# 04_HDMI_MIPI.net
KiCad netlist of a schematic drawn in Altium Designer
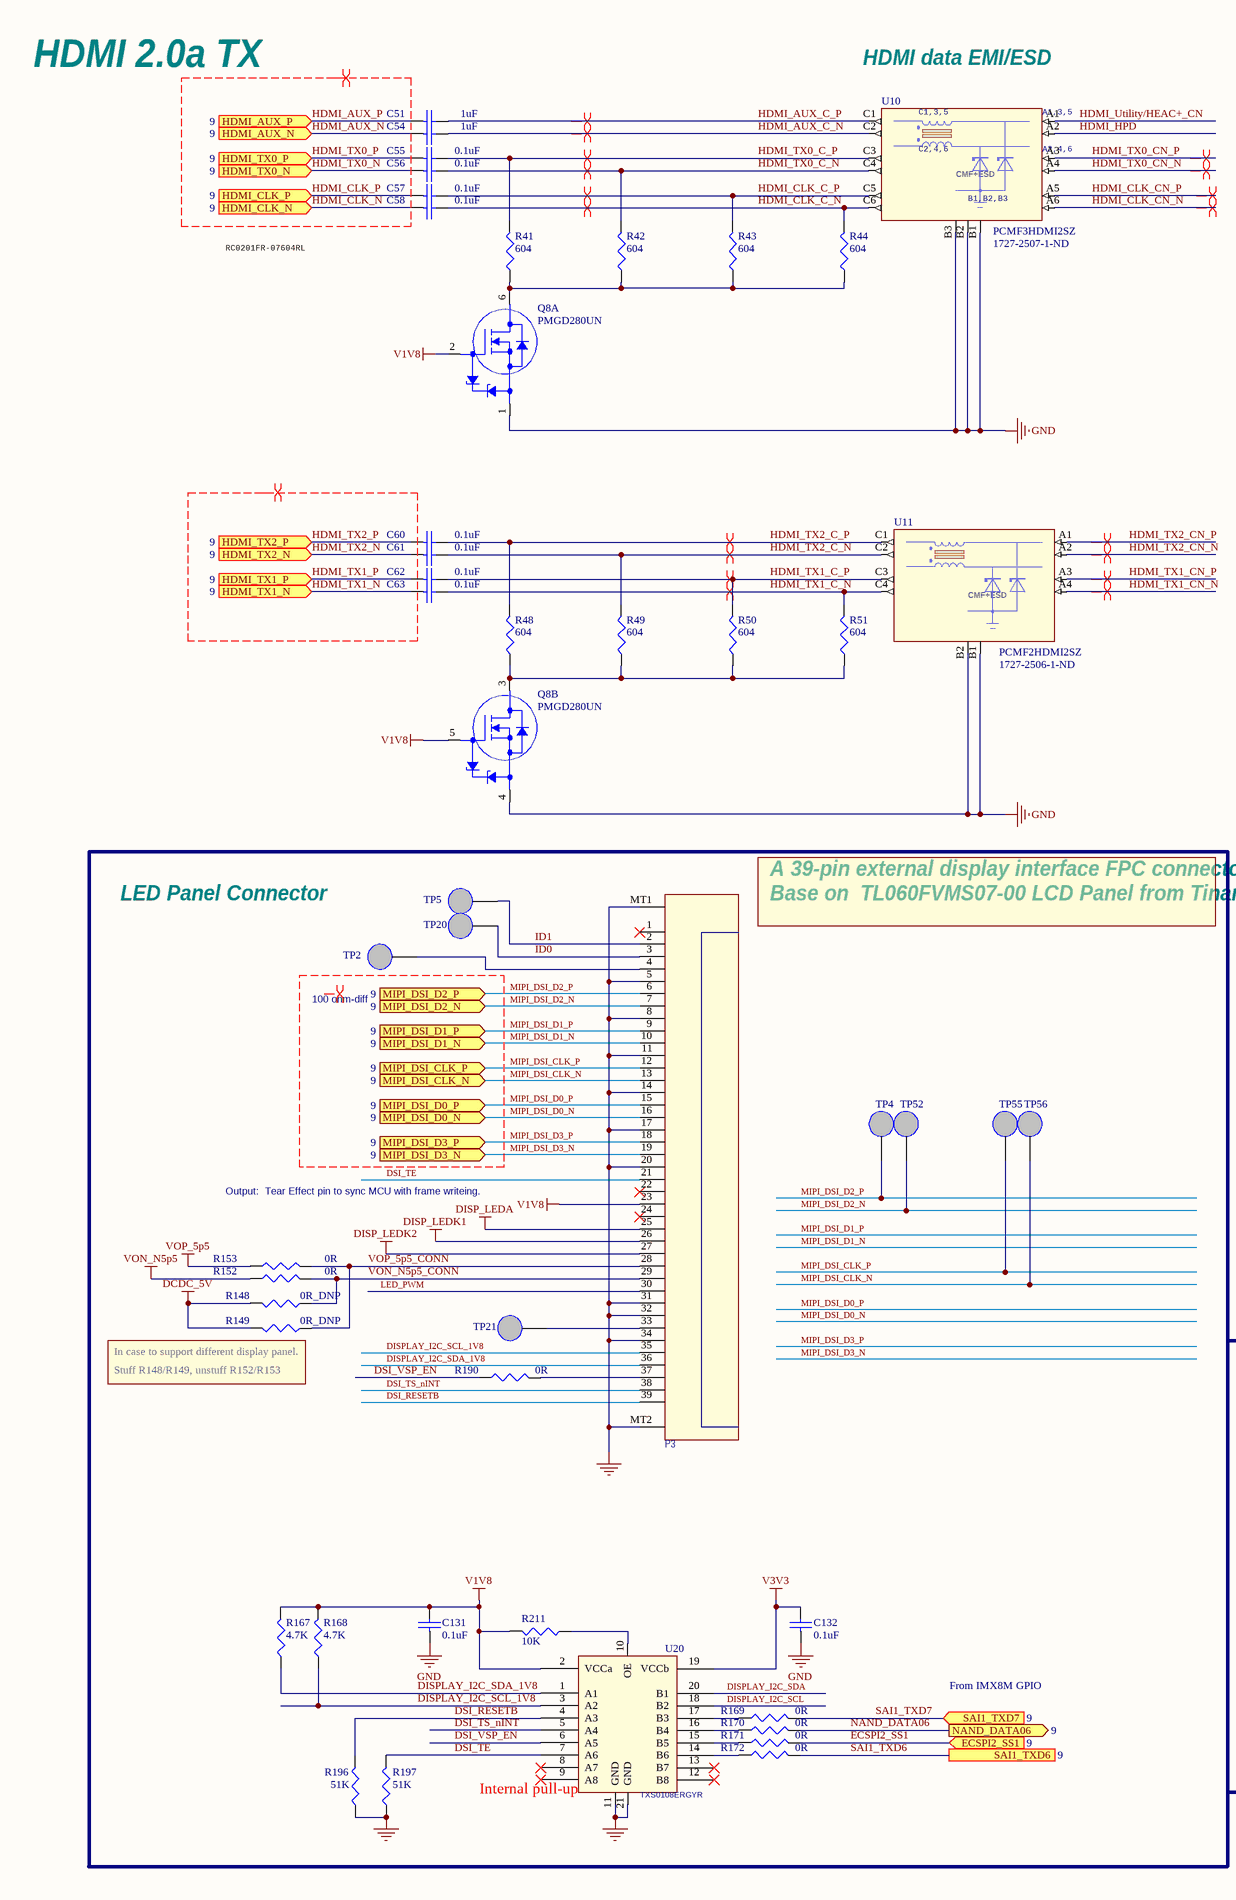
[diagram p0: 04_HDMI_MIPI.SchDoc, left]
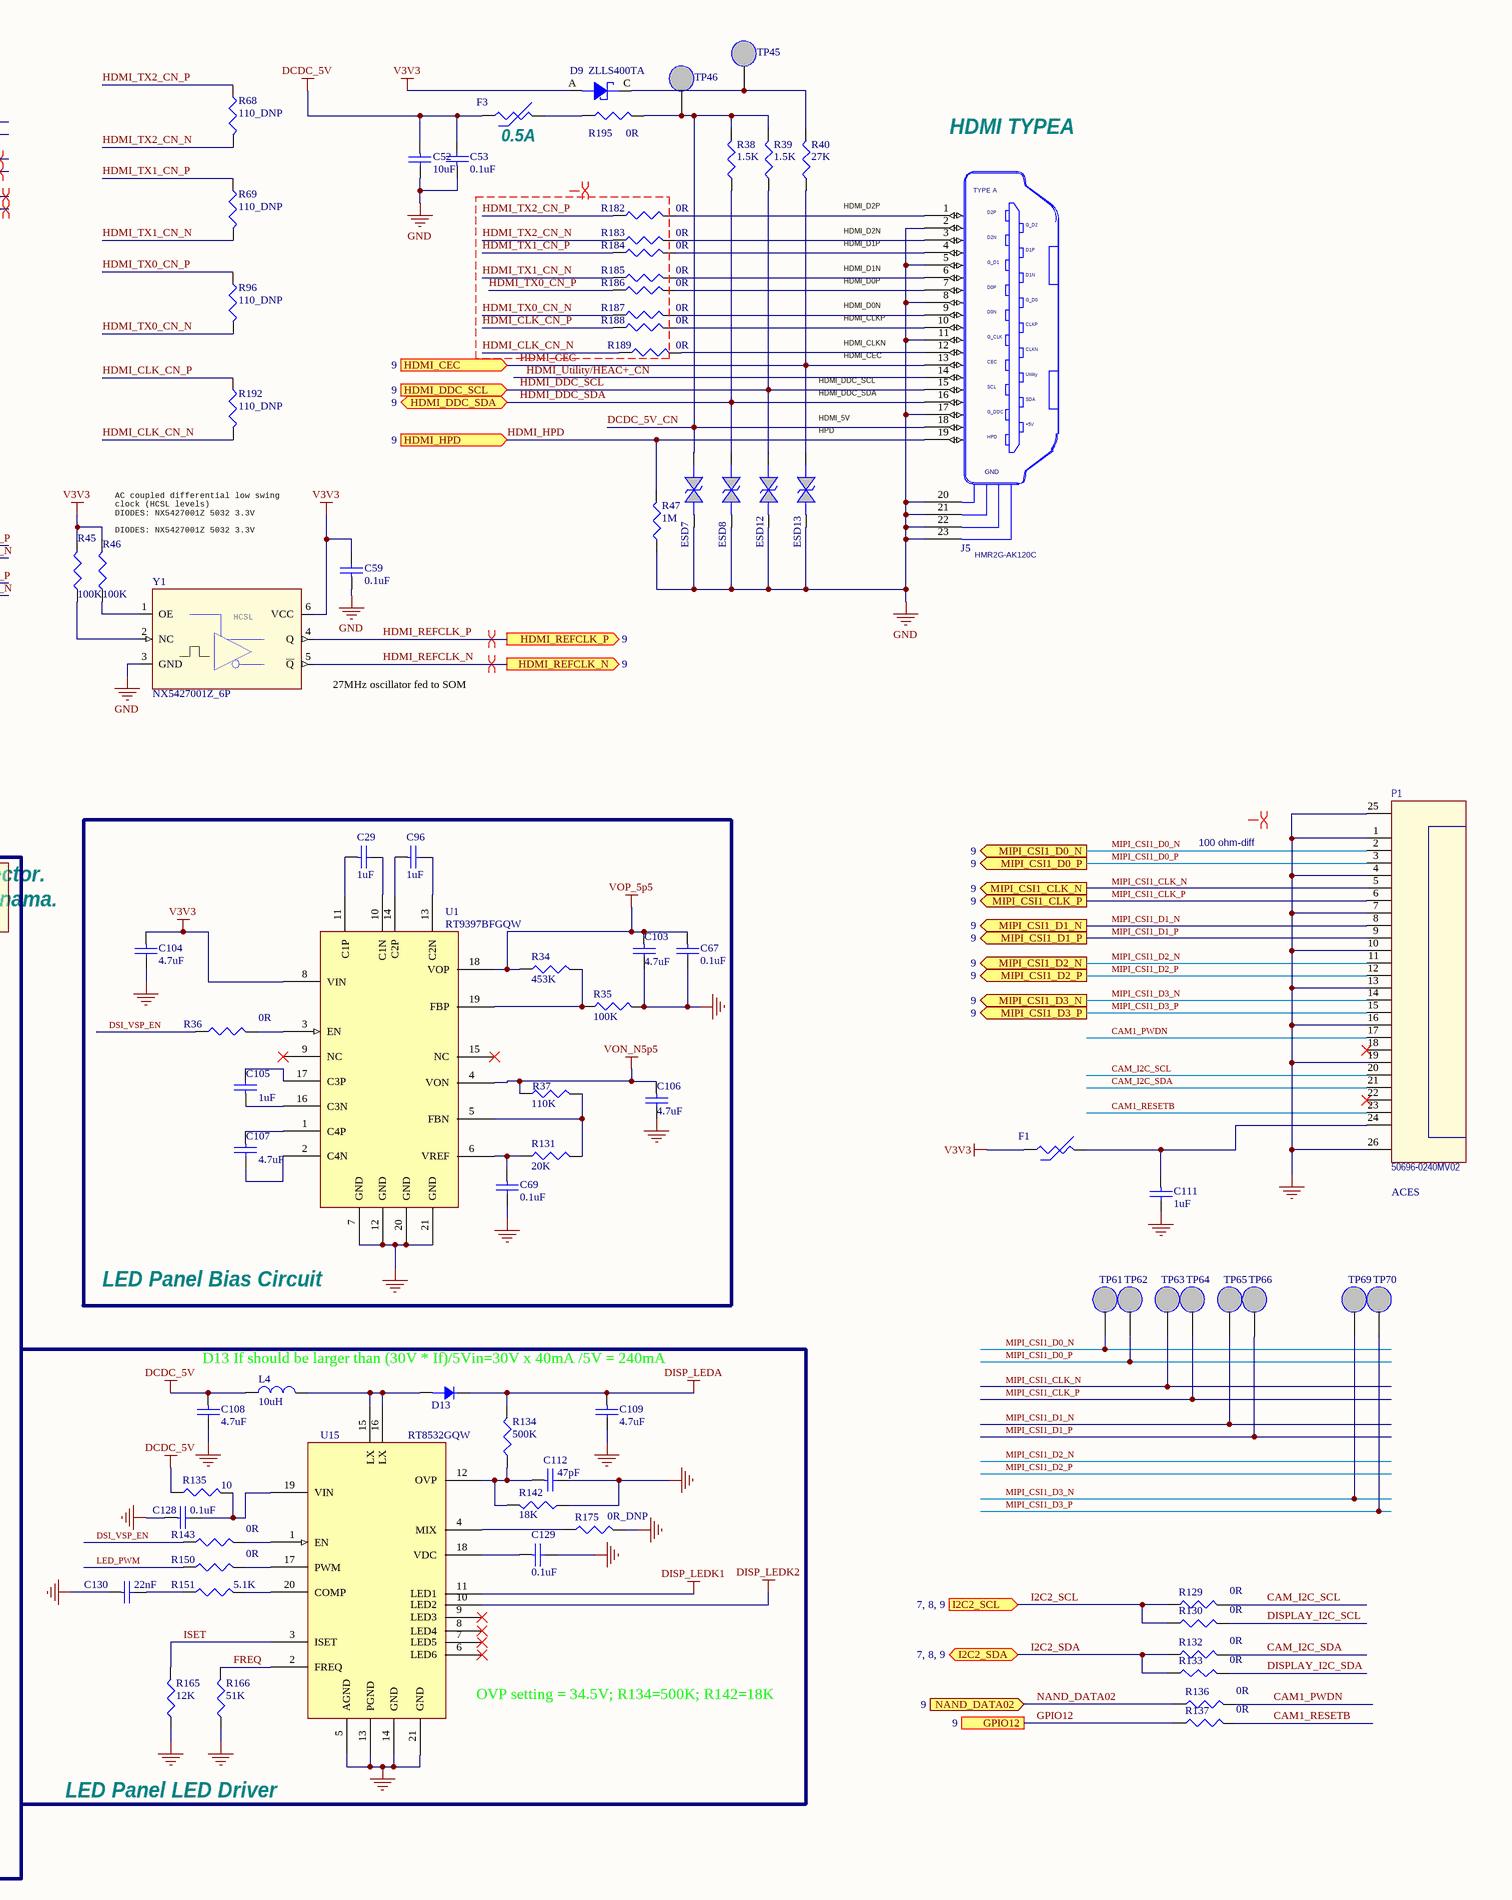
[diagram p1: 04_HDMI_MIPI.SchDoc, right]

(export (version "E")
  (design (tool "Eeschema 10.0.6"))
  (components
    (comp (ref "C29")
      (value "1uF")
      (footprint "0201")
      (description "CAP CER 1UF 6.3V 20% X5R 0201")
      (fields (field (name "MPN") "C0603X5R0J105M030BC") (field (name "Comment") "1uF/6.3V"))
      (libsource (lib "links") (part "CAP_0201_1.0uF"))
    )
    (comp (ref "C51")
      (value "1uF")
      (footprint "0402")
      (description "CAP CER 1.0UF 25V 10% X5R 0402")
      (fields (field (name "MPN") "TMK105BJ105MV-F") (field (name "Comment") "1uF/25V"))
      (libsource (lib "links") (part "CAP_0402_1.0uF_25V"))
    )
    (comp (ref "C52")
      (value "10uF")
      (footprint "0402")
      (description "CAP CER 10UF 10V 20% X5R 0402")
      (fields (field (name "MPN") "CL05A106MP5NUNC") (field (name "Comment") "10uF/10V"))
      (libsource (lib "links") (part "CAP_0402_10uF"))
    )
    (comp (ref "C53")
      (value "0.1uF")
      (footprint "0201")
      (description "CAP CER 0.1UF 10V 10% X5R 0201")
      (fields (field (name "MPN") "C0603X5R1A104K030BC") (field (name "Comment") "0.1uF/10V"))
      (libsource (lib "links") (part "CAP_0201_0.1uF"))
    )
    (comp (ref "C54")
      (value "1uF")
      (footprint "0402")
      (description "CAP CER 1.0UF 25V 10% X5R 0402")
      (fields (field (name "MPN") "TMK105BJ105MV-F") (field (name "Comment") "1uF/25V"))
      (libsource (lib "links") (part "CAP_0402_1.0uF_25V"))
    )
    (comp (ref "C55")
      (value "0.1uF")
      (footprint "0201")
      (description "CAP CER 0.1UF 10V 10% X5R 0201")
      (fields (field (name "MPN") "C0603X5R1A104K030BC") (field (name "Comment") "0.1uF/10V"))
      (libsource (lib "links") (part "CAP_0201_0.1uF"))
    )
    (comp (ref "C56")
      (value "0.1uF")
      (footprint "0201")
      (description "CAP CER 0.1UF 10V 10% X5R 0201")
      (fields (field (name "MPN") "C0603X5R1A104K030BC") (field (name "Comment") "0.1uF/10V"))
      (libsource (lib "links") (part "CAP_0201_0.1uF"))
    )
    (comp (ref "C57")
      (value "0.1uF")
      (footprint "0201")
      (description "CAP CER 0.1UF 10V 10% X5R 0201")
      (fields (field (name "MPN") "C0603X5R1A104K030BC") (field (name "Comment") "0.1uF/10V"))
      (libsource (lib "links") (part "CAP_0201_0.1uF"))
    )
    (comp (ref "C58")
      (value "0.1uF")
      (footprint "0201")
      (description "CAP CER 0.1UF 10V 10% X5R 0201")
      (fields (field (name "MPN") "C0603X5R1A104K030BC") (field (name "Comment") "0.1uF/10V"))
      (libsource (lib "links") (part "CAP_0201_0.1uF"))
    )
    (comp (ref "C59")
      (value "0.1uF")
      (footprint "0201")
      (description "CAP CER 0.1UF 10V 10% X5R 0201")
      (fields (field (name "MPN") "C0603X5R1A104K030BC") (field (name "Comment") "0.1uF/10V"))
      (libsource (lib "links") (part "CAP_0201_0.1uF"))
    )
    (comp (ref "C60")
      (value "0.1uF")
      (footprint "0201")
      (description "CAP CER 0.1UF 10V 10% X5R 0201")
      (fields (field (name "MPN") "C0603X5R1A104K030BC") (field (name "Comment") "0.1uF/10V"))
      (libsource (lib "links") (part "CAP_0201_0.1uF"))
    )
    (comp (ref "C61")
      (value "0.1uF")
      (footprint "0201")
      (description "CAP CER 0.1UF 10V 10% X5R 0201")
      (fields (field (name "MPN") "C0603X5R1A104K030BC") (field (name "Comment") "0.1uF/10V"))
      (libsource (lib "links") (part "CAP_0201_0.1uF"))
    )
    (comp (ref "C62")
      (value "0.1uF")
      (footprint "0201")
      (description "CAP CER 0.1UF 10V 10% X5R 0201")
      (fields (field (name "MPN") "C0603X5R1A104K030BC") (field (name "Comment") "0.1uF/10V"))
      (libsource (lib "links") (part "CAP_0201_0.1uF"))
    )
    (comp (ref "C63")
      (value "0.1uF")
      (footprint "0201")
      (description "CAP CER 0.1UF 10V 10% X5R 0201")
      (fields (field (name "MPN") "C0603X5R1A104K030BC") (field (name "Comment") "0.1uF/10V"))
      (libsource (lib "links") (part "CAP_0201_0.1uF"))
    )
    (comp (ref "C67")
      (value "0.1uF")
      (footprint "0201")
      (description "CAP CER 0.1UF 10V 10% X5R 0201")
      (fields (field (name "MPN") "C0603X5R1A104K030BC") (field (name "Comment") "0.1uF/10V"))
      (libsource (lib "links") (part "CAP_0201_0.1uF"))
    )
    (comp (ref "C69")
      (value "0.1uF")
      (footprint "0201")
      (description "CAP CER 0.1UF 10V 10% X5R 0201")
      (fields (field (name "MPN") "C0603X5R1A104K030BC") (field (name "Comment") "0.1uF/10V"))
      (libsource (lib "links") (part "CAP_0201_0.1uF"))
    )
    (comp (ref "C96")
      (value "1uF")
      (footprint "0201")
      (description "CAP CER 1UF 6.3V 20% X5R 0201")
      (fields (field (name "MPN") "C0603X5R0J105M030BC") (field (name "Comment") "1uF/6.3V"))
      (libsource (lib "links") (part "CAP_0201_1.0uF"))
    )
    (comp (ref "C103")
      (value "4.7uF")
      (footprint "0402")
      (description "CAP CER 4.7UF 10V 20% X5R 0402")
      (fields (field (name "MPN") "C1005X5R1A475M050BC") (field (name "Comment") "4.7uF/10V"))
      (libsource (lib "links") (part "CAP_0402_4.7uF"))
    )
    (comp (ref "C104")
      (value "4.7uF")
      (footprint "0402")
      (description "CAP CER 4.7UF 10V 20% X5R 0402")
      (fields (field (name "MPN") "C1005X5R1A475M050BC") (field (name "Comment") "4.7uF/10V"))
      (libsource (lib "links") (part "CAP_0402_4.7uF"))
    )
    (comp (ref "C105")
      (value "1uF")
      (footprint "0201")
      (description "CAP CER 1UF 6.3V 20% X5R 0201")
      (fields (field (name "MPN") "C0603X5R0J105M030BC") (field (name "Comment") "1uF/6.3V"))
      (libsource (lib "links") (part "CAP_0201_1.0uF"))
    )
    (comp (ref "C106")
      (value "4.7uF")
      (footprint "0402")
      (description "CAP CER 4.7UF 10V 20% X5R 0402")
      (fields (field (name "MPN") "C1005X5R1A475M050BC") (field (name "Comment") "4.7uF/10V"))
      (libsource (lib "links") (part "CAP_0402_4.7uF"))
    )
    (comp (ref "C107")
      (value "4.7uF")
      (footprint "0402")
      (description "CAP CER 4.7UF 10V 20% X5R 0402")
      (fields (field (name "MPN") "C1005X5R1A475M050BC") (field (name "Comment") "4.7uF/10V"))
      (libsource (lib "links") (part "CAP_0402_4.7uF"))
    )
    (comp (ref "C108")
      (value "4.7uF")
      (footprint "0402")
      (description "CAP CER 4.7UF 10V 20% X5R 0402")
      (fields (field (name "MPN") "C1005X5R1A475M050BC") (field (name "Comment") "4.7uF/10V"))
      (libsource (lib "links") (part "CAP_0402_4.7uF"))
    )
    (comp (ref "C109")
      (value "4.7uF")
      (footprint "0402")
      (description "CAP CER 4.7UF 10V 20% X5R 0402")
      (fields (field (name "MPN") "C1005X5R1A475M050BC") (field (name "Comment") "4.7uF/10V"))
      (libsource (lib "links") (part "CAP_0402_4.7uF"))
    )
    (comp (ref "C111")
      (value "1uF")
      (footprint "0201")
      (description "CAP CER 1UF 6.3V 20% X5R 0201")
      (fields (field (name "MPN") "C0603X5R0J105M030BC") (field (name "Comment") "1uF/6.3V"))
      (libsource (lib "links") (part "CAP_0201_1.0uF"))
    )
    (comp (ref "C112")
      (value "47pF")
      (footprint "0201")
      (description "CAP CER 47PF 25V 0201")
      (fields (field (name "MPN") "GRM0335C1E470FA01D") (field (name "Comment") "47pF/25V"))
      (libsource (lib "links") (part "CAP_0201_47pF"))
    )
    (comp (ref "C128")
      (value "0.1uF")
      (footprint "0201")
      (description "CAP CER 0.1UF 10V 10% X5R 0201")
      (fields (field (name "MPN") "C0603X5R1A104K030BC") (field (name "Comment") "0.1uF/10V"))
      (libsource (lib "links") (part "CAP_0201_0.1uF"))
    )
    (comp (ref "C129")
      (value "0.1uF")
      (footprint "0201")
      (description "CAP CER 0.1UF 10V 10% X5R 0201")
      (fields (field (name "MPN") "C0603X5R1A104K030BC") (field (name "Comment") "0.1uF/10V"))
      (libsource (lib "links") (part "CAP_0201_0.1uF"))
    )
    (comp (ref "C130")
      (value "22nF")
      (footprint "0201")
      (description "CAP CER 0.022UF 6.3V 10% X5R 0201")
      (fields (field (name "MPN") "CC0201KRX5R5BB223") (field (name "Comment") "22nF/6.3V"))
      (libsource (lib "links") (part "CAP_0201_22nF"))
    )
    (comp (ref "C131")
      (value "0.1uF")
      (footprint "0201")
      (description "CAP CER 0.1UF 10V 10% X5R 0201")
      (fields (field (name "MPN") "C0603X5R1A104K030BC") (field (name "Comment") "0.1uF/10V"))
      (libsource (lib "links") (part "CAP_0201_0.1uF"))
    )
    (comp (ref "C132")
      (value "0.1uF")
      (footprint "0201")
      (description "CAP CER 0.1UF 10V 10% X5R 0201")
      (fields (field (name "MPN") "C0603X5R1A104K030BC") (field (name "Comment") "0.1uF/10V"))
      (libsource (lib "links") (part "CAP_0201_0.1uF"))
    )
    (comp (ref "D9")
      (value "ZLLS400TA")
      (footprint "SOD323")
      (description "DIODE SCHOTTKY 40V 520MA SOD323")
      (libsource (lib "SpacePark") (part "DIODE_SCHTKY"))
    )
    (comp (ref "D13")
      (value "CUS10F30")
      (footprint "0805-Diode")
      (description "DIODE SCHOTTKY 20V 1A 0805")
      (libsource (lib "SpacePark") (part "Diode_Schottky_0805"))
    )
    (comp (ref "ESD7")
      (value "3.5pF/5V")
      (footprint "0201")
      (description "DIODE TVS 15kV 10V 50A 8pF SMT RoHS")
      (fields (field (name "MPN") "DESD5V0V1BCSP-7"))
      (libsource (lib "links") (part "DIODE BI-DIR TRIG"))
    )
    (comp (ref "ESD8")
      (value "3.5pF/5V")
      (footprint "0201")
      (description "DIODE TVS 15kV 10V 50A 8pF SMT RoHS")
      (fields (field (name "MPN") "DESD5V0V1BCSP-7"))
      (libsource (lib "links") (part "DIODE BI-DIR TRIG"))
    )
    (comp (ref "ESD12")
      (value "3.5pF/5V")
      (footprint "0201")
      (description "DIODE TVS 15kV 10V 50A 8pF SMT RoHS")
      (fields (field (name "MPN") "DESD5V0V1BCSP-7"))
      (libsource (lib "links") (part "DIODE BI-DIR TRIG"))
    )
    (comp (ref "ESD13")
      (value "3.5pF/5V")
      (footprint "0201")
      (description "DIODE TVS 15kV 10V 50A 8pF SMT RoHS")
      (fields (field (name "MPN") "DESD5V0V1BCSP-7"))
      (libsource (lib "links") (part "DIODE BI-DIR TRIG"))
    )
    (comp (ref "F1")
      (value "PTC_FUSE_0805_0p5A")
      (footprint "0805")
      (description "PTC FUSE 0.5A 0805")
      (libsource (lib "SpacePark") (part "PTC_FUSE_0805_0p5A"))
    )
    (comp (ref "F3")
      (value "PTC_FUSE_0805_0p5A")
      (footprint "0805")
      (description "PTC FUSE 0.5A 0805")
      (libsource (lib "SpacePark") (part "PTC_FUSE_0805_0p5A"))
    )
    (comp (ref "J5")
      (value "HMR2G-AK120C")
      (footprint "HDMI19-HMR2G-AK120C")
      (description "CONN RCPT 19POS HDMI DIP WO FLANGE")
      (libsource (lib "SpacePark") (part "CONN_HDMI_TYPEA_ACON_HMR2G-AK120C"))
    )
    (comp (ref "L4")
      (value "10uH")
      (footprint "AP3-00115")
      (description "FIXED IND 10UH 710MA 300 MOHM")
      (fields (field (name "MPN") "LQH3NPN100MJRL"))
      (libsource (lib "links") (part "INDUCTOR_LQH3NPN100MJ0"))
    )
    (comp (ref "P1")
      (value "50696-0240MV02")
      (footprint "FPC24-0_5-14_18x4_71MM")
      (description "Connector,FP, .5mm pitch, 24-pin, R/A,  SMT")
      (fields (field (name "QCI SUPPLIER") "ACES"))
      (libsource (lib "SpacePark") (part "CONN_ACES_50696-0240MV02"))
    )
    (comp (ref "P3")
      (value "FH26-39S-0.3SHW(05)")
      (footprint "FPC39-FH26W-39S-0_3SHW")
      (description "Connector,FP, .30mm pitch, 39-pin, R/A,  SMT")
      (libsource (lib "SpacePark") (part "CONN_FH26-39S-0.3SHW(0.5)"))
    )
    (comp (ref "Q8")
      (value "PMGD280UN")
      (footprint "SOT-363_0P65_SMT")
      (description "TRANS MOSFET (20V,0.87A,0.4W) SOT363")
      (libsource (lib "SpacePark") (part "TRAN_DUAL_NMOS_BSS138"))
    )
    (comp (ref "R34")
      (value "453K")
      (footprint "0201")
      (description "RES SMD 453K OHM JUMPER 1/20W  0201")
      (fields (field (name "MPN") "ERJ-1GEF4533C"))
      (libsource (lib "links") (part "R_0201_453K"))
    )
    (comp (ref "R35")
      (value "100K")
      (footprint "0201")
      (description "RES SMD 100K OHM JUMPER 1/20W  0201")
      (fields (field (name "MPN") "ERJ-1GEF1003C"))
      (libsource (lib "links") (part "R_0201_100K"))
    )
    (comp (ref "R36")
      (value "0R")
      (footprint "0201")
      (description "RES SMD 0.0OHM JUMPER 1/20W 0201")
      (fields (field (name "MPN") "ERJ-1GN0R00C"))
      (libsource (lib "links") (part "R_0201_0"))
    )
    (comp (ref "R37")
      (value "110K")
      (footprint "0201")
      (description "RES SMD 110K OHM  +/-1% 1/20W  0201")
      (fields (field (name "MPN") "ERJ-1GNF1103C"))
      (libsource (lib "links") (part "R_0201_110K"))
    )
    (comp (ref "R38")
      (value "1.5K")
      (footprint "0201")
      (description "RES SMD 1.5K OHM JUMPER 1/20W  0201")
      (fields (field (name "MPN") "ERJ-1GEJ6152C"))
      (libsource (lib "links") (part "R_0201_1.5K"))
    )
    (comp (ref "R39")
      (value "1.5K")
      (footprint "0201")
      (description "RES SMD 1.5K OHM JUMPER 1/20W  0201")
      (fields (field (name "MPN") "ERJ-1GEJ6152C"))
      (libsource (lib "links") (part "R_0201_1.5K"))
    )
    (comp (ref "R40")
      (value "27K")
      (footprint "0201")
      (description "RES SMD 27K OHM JUMPER 1/20W  0201")
      (fields (field (name "MPN") "ERJ-1GEF2702C"))
      (libsource (lib "links") (part "R_0201_27K"))
    )
    (comp (ref "R41")
      (value "604")
      (footprint "0201")
      (description "RES SMD 604 OHM JUMPER 1/20W  0201")
      (fields (field (name "MPN") "ERJ-1GEF6040C"))
      (libsource (lib "links") (part "R_0201_604"))
    )
    (comp (ref "R42")
      (value "604")
      (footprint "0201")
      (description "RES SMD 604 OHM JUMPER 1/20W  0201")
      (fields (field (name "MPN") "ERJ-1GEF6040C"))
      (libsource (lib "links") (part "R_0201_604"))
    )
    (comp (ref "R43")
      (value "604")
      (footprint "0201")
      (description "RES SMD 604 OHM JUMPER 1/20W  0201")
      (fields (field (name "MPN") "ERJ-1GEF6040C"))
      (libsource (lib "links") (part "R_0201_604"))
    )
    (comp (ref "R44")
      (value "604")
      (footprint "0201")
      (description "RES SMD 604 OHM JUMPER 1/20W  0201")
      (fields (field (name "MPN") "ERJ-1GEF6040C"))
      (libsource (lib "links") (part "R_0201_604"))
    )
    (comp (ref "R45")
      (value "100K")
      (footprint "0201")
      (description "RES SMD 100K OHM JUMPER 1/20W  0201")
      (fields (field (name "MPN") "ERJ-1GEF1003C"))
      (libsource (lib "links") (part "R_0201_100K"))
    )
    (comp (ref "R46")
      (value "100K")
      (footprint "0201")
      (description "RES SMD 100K OHM JUMPER 1/20W  0201")
      (fields (field (name "MPN") "ERJ-1GEF1003C"))
      (libsource (lib "links") (part "R_0201_100K"))
    )
    (comp (ref "R47")
      (value "1M")
      (footprint "0201")
      (description "RES SMD 1M OHM 1% 1/20W 0201")
      (fields (field (name "MPN") "ERJ-1GEF1004C"))
      (libsource (lib "links") (part "R_0201_1M"))
    )
    (comp (ref "R48")
      (value "604")
      (footprint "0201")
      (description "RES SMD 604 OHM JUMPER 1/20W  0201")
      (fields (field (name "MPN") "ERJ-1GEF6040C"))
      (libsource (lib "links") (part "R_0201_604"))
    )
    (comp (ref "R49")
      (value "604")
      (footprint "0201")
      (description "RES SMD 604 OHM JUMPER 1/20W  0201")
      (fields (field (name "MPN") "ERJ-1GEF6040C"))
      (libsource (lib "links") (part "R_0201_604"))
    )
    (comp (ref "R50")
      (value "604")
      (footprint "0201")
      (description "RES SMD 604 OHM JUMPER 1/20W  0201")
      (fields (field (name "MPN") "ERJ-1GEF6040C"))
      (libsource (lib "links") (part "R_0201_604"))
    )
    (comp (ref "R51")
      (value "604")
      (footprint "0201")
      (description "RES SMD 604 OHM JUMPER 1/20W  0201")
      (fields (field (name "MPN") "ERJ-1GEF6040C"))
      (libsource (lib "links") (part "R_0201_604"))
    )
    (comp (ref "R68")
      (value "110_DNP")
      (footprint "0201")
      (description "RES SMD 110 OHM 1% 1/20W 0201")
      (fields (field (name "MPN") "ERJ-1GEF1100C") (field (name "Comment") "110"))
      (libsource (lib "links") (part "R_0201_110"))
    )
    (comp (ref "R69")
      (value "110_DNP")
      (footprint "0201")
      (description "RES SMD 110 OHM 1% 1/20W 0201")
      (fields (field (name "MPN") "ERJ-1GEF1100C") (field (name "Comment") "110"))
      (libsource (lib "links") (part "R_0201_110"))
    )
    (comp (ref "R96")
      (value "110_DNP")
      (footprint "0201")
      (description "RES SMD 110 OHM 1% 1/20W 0201")
      (fields (field (name "MPN") "ERJ-1GEF1100C") (field (name "Comment") "110"))
      (libsource (lib "links") (part "R_0201_110"))
    )
    (comp (ref "R129")
      (value "0R")
      (footprint "0201")
      (description "RES SMD 0.0OHM JUMPER 1/20W 0201")
      (fields (field (name "MPN") "ERJ-1GN0R00C"))
      (libsource (lib "links") (part "R_0201_0"))
    )
    (comp (ref "R130")
      (value "0R")
      (footprint "0201")
      (description "RES SMD 0.0OHM JUMPER 1/20W 0201")
      (fields (field (name "MPN") "ERJ-1GN0R00C"))
      (libsource (lib "links") (part "R_0201_0"))
    )
    (comp (ref "R131")
      (value "20K")
      (footprint "0201")
      (description "RES SMD 20K OHM 1% 1/20W 0201")
      (fields (field (name "MPN") "ERJ-1GEF2002C"))
      (libsource (lib "links") (part "R_0201_20K"))
    )
    (comp (ref "R132")
      (value "0R")
      (footprint "0201")
      (description "RES SMD 0.0OHM JUMPER 1/20W 0201")
      (fields (field (name "MPN") "ERJ-1GN0R00C"))
      (libsource (lib "links") (part "R_0201_0"))
    )
    (comp (ref "R133")
      (value "0R")
      (footprint "0201")
      (description "RES SMD 0.0OHM JUMPER 1/20W 0201")
      (fields (field (name "MPN") "ERJ-1GN0R00C"))
      (libsource (lib "links") (part "R_0201_0"))
    )
    (comp (ref "R134")
      (value "500K")
      (footprint "0201")
      (description "RES SMD 499K OHM JUMPER 1/20W  0201")
      (fields (field (name "MPN") "ERJ-1GEF4993C"))
      (libsource (lib "links") (part "R_0201_499K"))
    )
    (comp (ref "R135")
      (value "10")
      (footprint "0201")
      (description "RES SMD 10 OHM 1% 1/20W 0201")
      (fields (field (name "MPN") "ERJ-1GEF10R0C"))
      (libsource (lib "links") (part "R_0201_10"))
    )
    (comp (ref "R136")
      (value "0R")
      (footprint "0201")
      (description "RES SMD 0.0OHM JUMPER 1/20W 0201")
      (fields (field (name "MPN") "ERJ-1GN0R00C"))
      (libsource (lib "links") (part "R_0201_0"))
    )
    (comp (ref "R137")
      (value "0R")
      (footprint "0201")
      (description "RES SMD 0.0OHM JUMPER 1/20W 0201")
      (fields (field (name "MPN") "ERJ-1GN0R00C"))
      (libsource (lib "links") (part "R_0201_0"))
    )
    (comp (ref "R142")
      (value "18K")
      (footprint "0201")
      (description "RES SMD 24K OHM 1% 1/20W 0201")
      (fields (field (name "MPN") "ERJ-1GEF2402C"))
      (libsource (lib "links") (part "R_0201_24K"))
    )
    (comp (ref "R143")
      (value "0R")
      (footprint "0201")
      (description "RES SMD 0.0OHM JUMPER 1/20W 0201")
      (fields (field (name "MPN") "ERJ-1GN0R00C"))
      (libsource (lib "links") (part "R_0201_0"))
    )
    (comp (ref "R148")
      (value "0R_DNP")
      (footprint "0603")
      (description "RES SMD 0.0 OHM JUMPER 1/4W 0603")
      (fields (field (name "MPN") "CRCW06030000Z0EAHP"))
      (libsource (lib "links") (part "R_0603_0"))
    )
    (comp (ref "R149")
      (value "0R_DNP")
      (footprint "0603")
      (description "RES SMD 0.0 OHM JUMPER 1/4W 0603")
      (fields (field (name "MPN") "CRCW06030000Z0EAHP"))
      (libsource (lib "links") (part "R_0603_0"))
    )
    (comp (ref "R150")
      (value "0R")
      (footprint "0201")
      (description "RES SMD 0.0OHM JUMPER 1/20W 0201")
      (fields (field (name "MPN") "ERJ-1GN0R00C"))
      (libsource (lib "links") (part "R_0201_0"))
    )
    (comp (ref "R151")
      (value "5.1K")
      (footprint "0201")
      (description "RES SMD 5.1K OHM JUMPER 1/20W  0201")
      (fields (field (name "MPN") "ERJ-JGEF5101C"))
      (libsource (lib "links") (part "R_0201_5.1K"))
    )
    (comp (ref "R152")
      (value "0R")
      (footprint "0603")
      (description "RES SMD 0.0 OHM JUMPER 1/4W 0603")
      (fields (field (name "MPN") "CRCW06030000Z0EAHP"))
      (libsource (lib "links") (part "R_0603_0"))
    )
    (comp (ref "R153")
      (value "0R")
      (footprint "0603")
      (description "RES SMD 0.0 OHM JUMPER 1/4W 0603")
      (fields (field (name "MPN") "CRCW06030000Z0EAHP"))
      (libsource (lib "links") (part "R_0603_0"))
    )
    (comp (ref "R165")
      (value "12K")
      (footprint "0402")
      (description "RES SMD 12K OHM 1% 1/10W 0402")
      (fields (field (name "MPN") "ERJ-2RKF1202X"))
      (libsource (lib "links") (part "R_0402_12k"))
    )
    (comp (ref "R166")
      (value "51K")
      (footprint "0201")
      (description "RES SMD 51K OHM 1% 1/20W 0201")
      (fields (field (name "MPN") "ERJ-1GEF5102C"))
      (libsource (lib "links") (part "R_0201_51K"))
    )
    (comp (ref "R167")
      (value "4.7K")
      (footprint "0402")
      (description "RES SMD 4.7K OHM 1% 1/10W 0402")
      (fields (field (name "MPN") "ERJ-2RKF4701X"))
      (libsource (lib "links") (part "R_0402_4.7k"))
    )
    (comp (ref "R168")
      (value "4.7K")
      (footprint "0402")
      (description "RES SMD 4.7K OHM 1% 1/10W 0402")
      (fields (field (name "MPN") "ERJ-2RKF4701X"))
      (libsource (lib "links") (part "R_0402_4.7k"))
    )
    (comp (ref "R169")
      (value "0R")
      (footprint "0201")
      (description "RES SMD 0.0OHM JUMPER 1/20W 0201")
      (fields (field (name "MPN") "ERJ-1GN0R00C"))
      (libsource (lib "links") (part "R_0201_0"))
    )
    (comp (ref "R170")
      (value "0R")
      (footprint "0201")
      (description "RES SMD 0.0OHM JUMPER 1/20W 0201")
      (fields (field (name "MPN") "ERJ-1GN0R00C"))
      (libsource (lib "links") (part "R_0201_0"))
    )
    (comp (ref "R171")
      (value "0R")
      (footprint "0201")
      (description "RES SMD 0.0OHM JUMPER 1/20W 0201")
      (fields (field (name "MPN") "ERJ-1GN0R00C"))
      (libsource (lib "links") (part "R_0201_0"))
    )
    (comp (ref "R172")
      (value "0R")
      (footprint "0201")
      (description "RES SMD 0.0OHM JUMPER 1/20W 0201")
      (fields (field (name "MPN") "ERJ-1GN0R00C"))
      (libsource (lib "links") (part "R_0201_0"))
    )
    (comp (ref "R175")
      (value "0R_DNP")
      (footprint "0201")
      (description "RES SMD 0.0OHM JUMPER 1/20W 0201")
      (fields (field (name "MPN") "ERJ-1GN0R00C"))
      (libsource (lib "links") (part "R_0201_0"))
    )
    (comp (ref "R182")
      (value "0R")
      (footprint "0201")
      (description "RES SMD 0.0OHM JUMPER 1/20W 0201")
      (fields (field (name "MPN") "ERJ-1GN0R00C"))
      (libsource (lib "links") (part "R_0201_0"))
    )
    (comp (ref "R183")
      (value "0R")
      (footprint "0201")
      (description "RES SMD 0.0OHM JUMPER 1/20W 0201")
      (fields (field (name "MPN") "ERJ-1GN0R00C"))
      (libsource (lib "links") (part "R_0201_0"))
    )
    (comp (ref "R184")
      (value "0R")
      (footprint "0201")
      (description "RES SMD 0.0OHM JUMPER 1/20W 0201")
      (fields (field (name "MPN") "ERJ-1GN0R00C"))
      (libsource (lib "links") (part "R_0201_0"))
    )
    (comp (ref "R185")
      (value "0R")
      (footprint "0201")
      (description "RES SMD 0.0OHM JUMPER 1/20W 0201")
      (fields (field (name "MPN") "ERJ-1GN0R00C"))
      (libsource (lib "links") (part "R_0201_0"))
    )
    (comp (ref "R186")
      (value "0R")
      (footprint "0201")
      (description "RES SMD 0.0OHM JUMPER 1/20W 0201")
      (fields (field (name "MPN") "ERJ-1GN0R00C"))
      (libsource (lib "links") (part "R_0201_0"))
    )
    (comp (ref "R187")
      (value "0R")
      (footprint "0201")
      (description "RES SMD 0.0OHM JUMPER 1/20W 0201")
      (fields (field (name "MPN") "ERJ-1GN0R00C"))
      (libsource (lib "links") (part "R_0201_0"))
    )
    (comp (ref "R188")
      (value "0R")
      (footprint "0201")
      (description "RES SMD 0.0OHM JUMPER 1/20W 0201")
      (fields (field (name "MPN") "ERJ-1GN0R00C"))
      (libsource (lib "links") (part "R_0201_0"))
    )
    (comp (ref "R189")
      (value "0R")
      (footprint "0201")
      (description "RES SMD 0.0OHM JUMPER 1/20W 0201")
      (fields (field (name "MPN") "ERJ-1GN0R00C"))
      (libsource (lib "links") (part "R_0201_0"))
    )
    (comp (ref "R190")
      (value "0R")
      (footprint "0201")
      (description "RES SMD 0.0OHM JUMPER 1/20W 0201")
      (fields (field (name "MPN") "ERJ-1GN0R00C") (field (name "Comment") "0R_DNP"))
      (libsource (lib "links") (part "R_0201_0"))
    )
    (comp (ref "R192")
      (value "110_DNP")
      (footprint "0201")
      (description "RES SMD 110 OHM 1% 1/20W 0201")
      (fields (field (name "MPN") "ERJ-1GEF1100C") (field (name "Comment") "110"))
      (libsource (lib "links") (part "R_0201_110"))
    )
    (comp (ref "R195")
      (value "0R")
      (footprint "0603")
      (description "RES SMD 0.0 OHM JUMPER 1/4W 0603")
      (fields (field (name "MPN") "CRCW06030000Z0EAHP"))
      (libsource (lib "links") (part "R_0603_0"))
    )
    (comp (ref "R196")
      (value "51K")
      (footprint "0201")
      (description "RES SMD 51K OHM 1% 1/20W 0201")
      (fields (field (name "MPN") "ERJ-1GEF5102C"))
      (libsource (lib "links") (part "R_0201_51K"))
    )
    (comp (ref "R197")
      (value "51K")
      (footprint "0201")
      (description "RES SMD 51K OHM 1% 1/20W 0201")
      (fields (field (name "MPN") "ERJ-1GEF5102C"))
      (libsource (lib "links") (part "R_0201_51K"))
    )
    (comp (ref "R211")
      (value "10K")
      (footprint "0201")
      (description "RES SMD 10K OHM JUMPER 1/20W  0201")
      (fields (field (name "MPN") "ERJ-1GEF103C"))
      (libsource (lib "links") (part "R_0201_10K"))
    )
    (comp (ref "TP2")
      (value "TP NM")
      (footprint "TP_SMD")
      (description "TEST POIN")
      (libsource (lib "links") (part "TP"))
    )
    (comp (ref "TP4")
      (value "TP NM")
      (footprint "TP2040")
      (description "TEST POINT (Large)")
      (libsource (lib "links") (part "TP_L"))
    )
    (comp (ref "TP5")
      (value "TP NM")
      (footprint "TP_SMD")
      (description "TEST POIN")
      (libsource (lib "links") (part "TP"))
    )
    (comp (ref "TP20")
      (value "TP NM")
      (footprint "TP_SMD")
      (description "TEST POIN")
      (libsource (lib "links") (part "TP"))
    )
    (comp (ref "TP21")
      (value "TP NM")
      (footprint "TP_SMD")
      (description "TEST POIN")
      (libsource (lib "links") (part "TP"))
    )
    (comp (ref "TP45")
      (value "TP NM")
      (footprint "TP_SMD_L")
      (description "TEST POINT (Large)")
      (libsource (lib "links") (part "TP_L"))
    )
    (comp (ref "TP46")
      (value "TP NM")
      (footprint "TP_SMD_L")
      (description "TEST POINT (Large)")
      (libsource (lib "links") (part "TP_L"))
    )
    (comp (ref "TP52")
      (value "TP NM")
      (footprint "TP2040")
      (description "TEST POINT (Large)")
      (libsource (lib "links") (part "TP_L"))
    )
    (comp (ref "TP55")
      (value "TP NM")
      (footprint "TP2040")
      (description "TEST POINT (Large)")
      (libsource (lib "links") (part "TP_L"))
    )
    (comp (ref "TP56")
      (value "TP NM")
      (footprint "TP2040")
      (description "TEST POINT (Large)")
      (libsource (lib "links") (part "TP_L"))
    )
    (comp (ref "TP61")
      (value "TP NM")
      (footprint "TP2040")
      (description "TEST POINT (Large)")
      (libsource (lib "links") (part "TP_L"))
    )
    (comp (ref "TP62")
      (value "TP NM")
      (footprint "TP2040")
      (description "TEST POINT (Large)")
      (libsource (lib "links") (part "TP_L"))
    )
    (comp (ref "TP63")
      (value "TP NM")
      (footprint "TP2040")
      (description "TEST POINT (Large)")
      (libsource (lib "links") (part "TP_L"))
    )
    (comp (ref "TP64")
      (value "TP NM")
      (footprint "TP2040")
      (description "TEST POINT (Large)")
      (libsource (lib "links") (part "TP_L"))
    )
    (comp (ref "TP65")
      (value "TP NM")
      (footprint "TP2040")
      (description "TEST POINT (Large)")
      (libsource (lib "links") (part "TP_L"))
    )
    (comp (ref "TP66")
      (value "TP NM")
      (footprint "TP2040")
      (description "TEST POINT (Large)")
      (libsource (lib "links") (part "TP_L"))
    )
    (comp (ref "TP69")
      (value "TP NM")
      (footprint "TP2040")
      (description "TEST POINT (Large)")
      (libsource (lib "links") (part "TP_L"))
    )
    (comp (ref "TP70")
      (value "TP NM")
      (footprint "TP2040")
      (description "TEST POINT (Large)")
      (libsource (lib "links") (part "TP_L"))
    )
    (comp (ref "U1")
      (value "RT9397BFGQW")
      (footprint "WQFN20-0_4-3_1x3_1-H0_8MM-1")
      (description "IC, Charge Pump Controller, WQFN20")
      (libsource (lib "SpacePark") (part "RT9397BF"))
    )
    (comp (ref "U10")
      (value "PCMF3HDMI2SZ")
      (footprint "WLCSP15_0P4_2P42X1P22_SMDP")
      (fields (field (name "SUPPLIER PART NUMBER 1") "1727-2507-1-ND"))
      (libsource (lib "SpacePark") (part "PCMF3HDMI2SZ"))
    )
    (comp (ref "U11")
      (value "PCMF2HDMI2SZ")
      (footprint "WLCSP10_0P4_1P2X1P6MM_SMDP")
      (fields (field (name "SUPPLIER PART NUMBER 1") "1727-2506-1-ND"))
      (libsource (lib "SpacePark") (part "PCMF2HDMI2SZ"))
    )
    (comp (ref "U15")
      (value "RT8532GQW")
      (footprint "WQFN20-0_4-3_1x3_1-H0_8MM-2")
      (description "IC, 6-string 43V White LED drivers with Boost Regulator, WQFN20")
      (libsource (lib "SpacePark") (part "RT8532"))
    )
    (comp (ref "U20")
      (value "TXS0108ERGYR")
      (footprint "VQFN20-0_5-4_65X3_65MM-H1MM")
      (description "Voltage Level Translator Bidirectional 1 Circuit 8 Channel 60Mbps 20-VQFN (3.5x4.5)")
      (libsource (lib "links") (part "TXS0108ERGYR"))
    )
    (comp (ref "Y1")
      (value "NX5427001Z_6P")
      (footprint "OSC6_1P27_5P2X3P4")
      (libsource (lib "SpacePark") (part "NX5427001Z_6P"))
    )
  )
  (nets
    (net (code "1") (name "/CAM1_PWDN") (class "Default")
      (node (ref "P1") (pin "17") (pintype "passive"))
      (node (ref "R136") (pin "2") (pintype "passive"))
    )
    (net (code "2") (name "/CAM1_RESETB") (class "Default")
      (node (ref "P1") (pin "23") (pintype "passive"))
      (node (ref "R137") (pin "2") (pintype "passive"))
    )
    (net (code "3") (name "/CAM_I2C_SCL") (class "Default")
      (node (ref "P1") (pin "20") (pintype "passive"))
      (node (ref "R129") (pin "2") (pintype "passive"))
    )
    (net (code "4") (name "/CAM_I2C_SDA") (class "Default")
      (node (ref "P1") (pin "21") (pintype "passive"))
      (node (ref "R132") (pin "2") (pintype "passive"))
    )
    (net (code "5") (name "/DCDC_5V_CN") (class "Default")
      (node (ref "ESD7") (pin "2") (pinfunction "2_2") (pintype "passive"))
      (node (ref "J5") (pin "18") (pinfunction "+5V_18") (pintype "bidirectional"))
      (node (ref "R195") (pin "2") (pintype "passive"))
      (node (ref "R38") (pin "2") (pintype "passive"))
      (node (ref "R39") (pin "2") (pintype "passive"))
      (node (ref "TP46") (pin "1") (pinfunction "1_1") (pintype "passive"))
    )
    (net (code "6") (name "/DISPLAY_I2C_SCL") (class "Default")
      (node (ref "R130") (pin "2") (pintype "passive"))
      (node (ref "U20") (pin "18") (pinfunction "B2_18") (pintype "passive"))
    )
    (net (code "7") (name "/DISPLAY_I2C_SCL_1V8") (class "Default")
      (node (ref "P3") (pin "35") (pintype "passive"))
      (node (ref "R168") (pin "1") (pintype "passive"))
      (node (ref "U20") (pin "3") (pinfunction "A2_3") (pintype "passive"))
    )
    (net (code "8") (name "/DISPLAY_I2C_SDA") (class "Default")
      (node (ref "R133") (pin "2") (pintype "passive"))
      (node (ref "U20") (pin "20") (pinfunction "B1_20") (pintype "passive"))
    )
    (net (code "9") (name "/DISPLAY_I2C_SDA_1V8") (class "Default")
      (node (ref "P3") (pin "36") (pintype "passive"))
      (node (ref "R167") (pin "1") (pintype "passive"))
      (node (ref "U20") (pin "1") (pinfunction "A1_1") (pintype "passive"))
    )
    (net (code "10") (name "/DSI_RESETB") (class "Default")
      (node (ref "P3") (pin "39") (pintype "passive"))
      (node (ref "R196") (pin "2") (pintype "passive"))
      (node (ref "U20") (pin "4") (pinfunction "A3_4") (pintype "passive"))
    )
    (net (code "11") (name "/DSI_TE") (class "Default")
      (node (ref "P3") (pin "21") (pintype "passive"))
      (node (ref "R197") (pin "2") (pintype "passive"))
      (node (ref "U20") (pin "7") (pinfunction "A6_7") (pintype "passive"))
    )
    (net (code "12") (name "/DSI_TS_nINT") (class "Default")
      (node (ref "P3") (pin "38") (pintype "passive"))
      (node (ref "U20") (pin "5") (pinfunction "A4_5") (pintype "passive"))
    )
    (net (code "13") (name "/DSI_VSP_EN") (class "Default")
      (node (ref "R143") (pin "1") (pintype "passive"))
      (node (ref "R190") (pin "1") (pintype "passive"))
      (node (ref "R36") (pin "1") (pintype "passive"))
      (node (ref "U20") (pin "6") (pinfunction "A5_6") (pintype "passive"))
    )
    (net (code "14") (name "/ECSPI2_SS1") (class "Default") (node (ref "R171") (pin "2") (pintype "passive")))
    (net (code "15") (name "/FREQ") (class "Default")
      (node (ref "R166") (pin "2") (pintype "passive"))
      (node (ref "U15") (pin "2") (pinfunction "FREQ_2") (pintype "passive"))
    )
    (net (code "16") (name "/GPIO12") (class "Default") (node (ref "R137") (pin "1") (pintype "passive")))
    (net (code "17") (name "/HDMI_AUX_C_N") (class "Default")
      (node (ref "C54") (pin "2") (pinfunction "2_2") (pintype "passive"))
      (node (ref "U10") (pin "C2") (pinfunction "CH1_OUT-_C2") (pintype "output"))
    )
    (net (code "18") (name "/HDMI_AUX_C_P") (class "Default")
      (node (ref "C51") (pin "2") (pinfunction "2_2") (pintype "passive"))
      (node (ref "U10") (pin "C1") (pinfunction "CH1_OUT+_C1") (pintype "output"))
    )
    (net (code "19") (name "/HDMI_AUX_N") (class "Default")
      (node (ref "C54") (pin "1") (pinfunction "1_1") (pintype "passive"))
    )
    (net (code "20") (name "/HDMI_AUX_P") (class "Default")
      (node (ref "C51") (pin "1") (pinfunction "1_1") (pintype "passive"))
    )
    (net (code "21") (name "/HDMI_CEC") (class "Default")
      (node (ref "ESD13") (pin "2") (pinfunction "2_2") (pintype "passive"))
      (node (ref "J5") (pin "13") (pinfunction "CEC_13") (pintype "bidirectional"))
      (node (ref "R40") (pin "1") (pintype "passive"))
    )
    (net (code "22") (name "/HDMI_CLK_CN_N") (class "Default")
      (node (ref "R189") (pin "1") (pintype "passive"))
      (node (ref "R192") (pin "2") (pintype "passive"))
      (node (ref "U10") (pin "A6") (pinfunction "CH3_IN-_A6") (pintype "input"))
    )
    (net (code "23") (name "/HDMI_CLK_CN_P") (class "Default")
      (node (ref "R188") (pin "1") (pintype "passive"))
      (node (ref "R192") (pin "1") (pintype "passive"))
      (node (ref "U10") (pin "A5") (pinfunction "CH3_IN+_A5") (pintype "input"))
    )
    (net (code "24") (name "/HDMI_CLK_C_N") (class "Default")
      (node (ref "C58") (pin "2") (pinfunction "2_2") (pintype "passive"))
      (node (ref "R44") (pin "2") (pintype "passive"))
      (node (ref "U10") (pin "C6") (pinfunction "CH3_OUT-_C6") (pintype "output"))
    )
    (net (code "25") (name "/HDMI_CLK_C_P") (class "Default")
      (node (ref "C57") (pin "2") (pinfunction "2_2") (pintype "passive"))
      (node (ref "R43") (pin "2") (pintype "passive"))
      (node (ref "U10") (pin "C5") (pinfunction "CH3_OUT+_C5") (pintype "output"))
    )
    (net (code "26") (name "/HDMI_CLK_N") (class "Default")
      (node (ref "C58") (pin "1") (pinfunction "1_1") (pintype "passive"))
    )
    (net (code "27") (name "/HDMI_CLK_P") (class "Default")
      (node (ref "C57") (pin "1") (pinfunction "1_1") (pintype "passive"))
    )
    (net (code "28") (name "/HDMI_DDC_SCL") (class "Default")
      (node (ref "ESD12") (pin "2") (pinfunction "2_2") (pintype "passive"))
      (node (ref "J5") (pin "15") (pinfunction "SCL_15") (pintype "bidirectional"))
      (node (ref "R39") (pin "1") (pintype "passive"))
    )
    (net (code "29") (name "/HDMI_DDC_SDA") (class "Default")
      (node (ref "ESD8") (pin "2") (pinfunction "2_2") (pintype "passive"))
      (node (ref "J5") (pin "16") (pinfunction "SDA_16") (pintype "bidirectional"))
      (node (ref "R38") (pin "1") (pintype "passive"))
    )
    (net (code "30") (name "/HDMI_HPD") (class "Default")
      (node (ref "J5") (pin "19") (pinfunction "HPD_19") (pintype "bidirectional"))
      (node (ref "R47") (pin "2") (pintype "passive"))
      (node (ref "U10") (pin "A2") (pinfunction "CH1_IN-_A2") (pintype "input"))
    )
    (net (code "31") (name "/HDMI_REFCLK_N") (class "Default")
      (node (ref "Y1") (pin "5") (pinfunction "~{Q}_5") (pintype "output"))
    )
    (net (code "32") (name "/HDMI_REFCLK_P") (class "Default")
      (node (ref "Y1") (pin "4") (pinfunction "Q_4") (pintype "output"))
    )
    (net (code "33") (name "/HDMI_TX0_CN_N") (class "Default")
      (node (ref "R187") (pin "1") (pintype "passive"))
      (node (ref "R96") (pin "2") (pintype "passive"))
      (node (ref "U10") (pin "A4") (pinfunction "CH2_IN-_A4") (pintype "input"))
    )
    (net (code "34") (name "/HDMI_TX0_CN_P") (class "Default")
      (node (ref "R186") (pin "1") (pintype "passive"))
      (node (ref "R96") (pin "1") (pintype "passive"))
      (node (ref "U10") (pin "A3") (pinfunction "CH2_IN+_A3") (pintype "input"))
    )
    (net (code "35") (name "/HDMI_TX0_C_N") (class "Default")
      (node (ref "C56") (pin "2") (pinfunction "2_2") (pintype "passive"))
      (node (ref "R42") (pin "2") (pintype "passive"))
      (node (ref "U10") (pin "C4") (pinfunction "CH2_OUT-_C4") (pintype "output"))
    )
    (net (code "36") (name "/HDMI_TX0_C_P") (class "Default")
      (node (ref "C55") (pin "2") (pinfunction "2_2") (pintype "passive"))
      (node (ref "R41") (pin "2") (pintype "passive"))
      (node (ref "U10") (pin "C3") (pinfunction "CH2_OUT+_C3") (pintype "output"))
    )
    (net (code "37") (name "/HDMI_TX0_N") (class "Default")
      (node (ref "C56") (pin "1") (pinfunction "1_1") (pintype "passive"))
    )
    (net (code "38") (name "/HDMI_TX0_P") (class "Default")
      (node (ref "C55") (pin "1") (pinfunction "1_1") (pintype "passive"))
    )
    (net (code "39") (name "/HDMI_TX1_CN_N") (class "Default")
      (node (ref "R185") (pin "1") (pintype "passive"))
      (node (ref "R69") (pin "2") (pintype "passive"))
      (node (ref "U11") (pin "A4") (pinfunction "CH2_IN-_A4") (pintype "input"))
    )
    (net (code "40") (name "/HDMI_TX1_CN_P") (class "Default")
      (node (ref "R184") (pin "1") (pintype "passive"))
      (node (ref "R69") (pin "1") (pintype "passive"))
      (node (ref "U11") (pin "A3") (pinfunction "CH2_IN+_A3") (pintype "input"))
    )
    (net (code "41") (name "/HDMI_TX1_C_N") (class "Default")
      (node (ref "C63") (pin "2") (pinfunction "2_2") (pintype "passive"))
      (node (ref "R51") (pin "2") (pintype "passive"))
      (node (ref "U11") (pin "C4") (pinfunction "CH2_OUT-_C4") (pintype "output"))
    )
    (net (code "42") (name "/HDMI_TX1_C_P") (class "Default")
      (node (ref "C62") (pin "2") (pinfunction "2_2") (pintype "passive"))
      (node (ref "R50") (pin "2") (pintype "passive"))
      (node (ref "U11") (pin "C3") (pinfunction "CH2_OUT+_C3") (pintype "output"))
    )
    (net (code "43") (name "/HDMI_TX1_N") (class "Default")
      (node (ref "C63") (pin "1") (pinfunction "1_1") (pintype "passive"))
    )
    (net (code "44") (name "/HDMI_TX1_P") (class "Default")
      (node (ref "C62") (pin "1") (pinfunction "1_1") (pintype "passive"))
    )
    (net (code "45") (name "/HDMI_TX2_CN_N") (class "Default")
      (node (ref "R183") (pin "1") (pintype "passive"))
      (node (ref "R68") (pin "2") (pintype "passive"))
      (node (ref "U11") (pin "A2") (pinfunction "CH1_IN-_A2") (pintype "input"))
    )
    (net (code "46") (name "/HDMI_TX2_CN_P") (class "Default")
      (node (ref "R182") (pin "1") (pintype "passive"))
      (node (ref "R68") (pin "1") (pintype "passive"))
      (node (ref "U11") (pin "A1") (pinfunction "CH1_IN+_A1") (pintype "input"))
    )
    (net (code "47") (name "/HDMI_TX2_C_N") (class "Default")
      (node (ref "C61") (pin "2") (pinfunction "2_2") (pintype "passive"))
      (node (ref "R49") (pin "2") (pintype "passive"))
      (node (ref "U11") (pin "C2") (pinfunction "CH1_OUT-_C2") (pintype "output"))
    )
    (net (code "48") (name "/HDMI_TX2_C_P") (class "Default")
      (node (ref "C60") (pin "2") (pinfunction "2_2") (pintype "passive"))
      (node (ref "R48") (pin "2") (pintype "passive"))
      (node (ref "U11") (pin "C1") (pinfunction "CH1_OUT+_C1") (pintype "output"))
    )
    (net (code "49") (name "/HDMI_TX2_N") (class "Default")
      (node (ref "C61") (pin "1") (pinfunction "1_1") (pintype "passive"))
    )
    (net (code "50") (name "/HDMI_TX2_P") (class "Default")
      (node (ref "C60") (pin "1") (pinfunction "1_1") (pintype "passive"))
    )
    (net (code "51") (name "/HDMI_Utility{slash}HEAC+_CN") (class "Default")
      (node (ref "J5") (pin "14") (pinfunction "Utility_14") (pintype "bidirectional"))
      (node (ref "U10") (pin "A1") (pinfunction "CH1_IN+_A1") (pintype "input"))
    )
    (net (code "52") (name "/I2C2_SCL") (class "Default")
      (node (ref "R129") (pin "1") (pintype "passive"))
      (node (ref "R130") (pin "1") (pintype "passive"))
    )
    (net (code "53") (name "/I2C2_SDA") (class "Default")
      (node (ref "R132") (pin "1") (pintype "passive"))
      (node (ref "R133") (pin "1") (pintype "passive"))
    )
    (net (code "54") (name "/ID0") (class "Default")
      (node (ref "P3") (pin "3") (pintype "passive"))
      (node (ref "TP20") (pin "1") (pinfunction "1_1") (pintype "passive"))
    )
    (net (code "55") (name "/ID1") (class "Default")
      (node (ref "P3") (pin "2") (pintype "passive"))
      (node (ref "TP5") (pin "1") (pinfunction "1_1") (pintype "passive"))
    )
    (net (code "56") (name "/ISET") (class "Default")
      (node (ref "R165") (pin "2") (pintype "passive"))
      (node (ref "U15") (pin "3") (pinfunction "ISET_3") (pintype "passive"))
    )
    (net (code "57") (name "/LED_PWM") (class "Default")
      (node (ref "P3") (pin "30") (pintype "passive"))
      (node (ref "R150") (pin "1") (pintype "passive"))
    )
    (net (code "58") (name "/MIPI_CSI1_CLK_N") (class "Default")
      (node (ref "P1") (pin "5") (pintype "passive"))
      (node (ref "TP63") (pin "1") (pinfunction "1_1") (pintype "passive"))
    )
    (net (code "59") (name "/MIPI_CSI1_CLK_P") (class "Default")
      (node (ref "P1") (pin "6") (pintype "passive"))
      (node (ref "TP64") (pin "1") (pinfunction "1_1") (pintype "passive"))
    )
    (net (code "60") (name "/MIPI_CSI1_D0_N") (class "Default")
      (node (ref "P1") (pin "2") (pintype "passive"))
      (node (ref "TP61") (pin "1") (pinfunction "1_1") (pintype "passive"))
    )
    (net (code "61") (name "/MIPI_CSI1_D0_P") (class "Default")
      (node (ref "P1") (pin "3") (pintype "passive"))
      (node (ref "TP62") (pin "1") (pinfunction "1_1") (pintype "passive"))
    )
    (net (code "62") (name "/MIPI_CSI1_D1_N") (class "Default")
      (node (ref "P1") (pin "8") (pintype "passive"))
      (node (ref "TP65") (pin "1") (pinfunction "1_1") (pintype "passive"))
    )
    (net (code "63") (name "/MIPI_CSI1_D1_P") (class "Default")
      (node (ref "P1") (pin "9") (pintype "passive"))
      (node (ref "TP66") (pin "1") (pinfunction "1_1") (pintype "passive"))
    )
    (net (code "64") (name "/MIPI_CSI1_D2_N") (class "Default")
      (node (ref "P1") (pin "11") (pintype "passive"))
    )
    (net (code "65") (name "/MIPI_CSI1_D2_P") (class "Default")
      (node (ref "P1") (pin "12") (pintype "passive"))
    )
    (net (code "66") (name "/MIPI_CSI1_D3_N") (class "Default")
      (node (ref "P1") (pin "14") (pintype "passive"))
      (node (ref "TP69") (pin "1") (pinfunction "1_1") (pintype "passive"))
    )
    (net (code "67") (name "/MIPI_CSI1_D3_P") (class "Default")
      (node (ref "P1") (pin "15") (pintype "passive"))
      (node (ref "TP70") (pin "1") (pinfunction "1_1") (pintype "passive"))
    )
    (net (code "68") (name "/MIPI_DSI_CLK_N") (class "Default")
      (node (ref "P3") (pin "13") (pintype "passive"))
      (node (ref "TP56") (pin "1") (pinfunction "1_1") (pintype "passive"))
    )
    (net (code "69") (name "/MIPI_DSI_CLK_P") (class "Default")
      (node (ref "P3") (pin "12") (pintype "passive"))
      (node (ref "TP55") (pin "1") (pinfunction "1_1") (pintype "passive"))
    )
    (net (code "70") (name "/MIPI_DSI_D0_N") (class "Default")
      (node (ref "P3") (pin "16") (pintype "passive"))
    )
    (net (code "71") (name "/MIPI_DSI_D0_P") (class "Default")
      (node (ref "P3") (pin "15") (pintype "passive"))
    )
    (net (code "72") (name "/MIPI_DSI_D1_N") (class "Default")
      (node (ref "P3") (pin "10") (pintype "passive"))
    )
    (net (code "73") (name "/MIPI_DSI_D1_P") (class "Default")
      (node (ref "P3") (pin "9") (pintype "passive"))
    )
    (net (code "74") (name "/MIPI_DSI_D2_N") (class "Default")
      (node (ref "P3") (pin "7") (pintype "passive"))
      (node (ref "TP52") (pin "1") (pinfunction "1_1") (pintype "passive"))
    )
    (net (code "75") (name "/MIPI_DSI_D2_P") (class "Default")
      (node (ref "P3") (pin "6") (pintype "passive"))
      (node (ref "TP4") (pin "1") (pinfunction "1_1") (pintype "passive"))
    )
    (net (code "76") (name "/MIPI_DSI_D3_N") (class "Default")
      (node (ref "P3") (pin "19") (pintype "passive"))
    )
    (net (code "77") (name "/MIPI_DSI_D3_P") (class "Default")
      (node (ref "P3") (pin "18") (pintype "passive"))
    )
    (net (code "78") (name "/NAND_DATA02") (class "Default")
      (node (ref "R136") (pin "1") (pintype "passive"))
    )
    (net (code "79") (name "/NAND_DATA06") (class "Default")
      (node (ref "R170") (pin "2") (pintype "passive"))
    )
    (net (code "80") (name "/SAI1_TXD6") (class "Default") (node (ref "R172") (pin "2") (pintype "passive")))
    (net (code "81") (name "/SAI1_TXD7") (class "Default") (node (ref "R169") (pin "2") (pintype "passive")))
    (net (code "82") (name "/VON_N5p5_CONN") (class "Default")
      (node (ref "P3") (pin "29") (pintype "passive"))
      (node (ref "R148") (pin "1") (pintype "passive"))
      (node (ref "R152") (pin "2") (pintype "passive"))
    )
    (net (code "83") (name "/VOP_5p5_CONN") (class "Default")
      (node (ref "P3") (pin "28") (pintype "passive"))
      (node (ref "R149") (pin "1") (pintype "passive"))
      (node (ref "R153") (pin "2") (pintype "passive"))
    )
    (net (code "84") (name "DCDC_5V") (class "Default")
      (node (ref "C108") (pin "1") (pinfunction "1_1") (pintype "passive"))
      (node (ref "C52") (pin "1") (pinfunction "1_1") (pintype "passive"))
      (node (ref "C53") (pin "2") (pinfunction "2_2") (pintype "passive"))
      (node (ref "F3") (pin "1") (pintype "passive"))
      (node (ref "L4") (pin "1") (pinfunction "1_1") (pintype "passive"))
      (node (ref "R135") (pin "1") (pintype "passive"))
      (node (ref "R148") (pin "2") (pintype "passive"))
      (node (ref "R149") (pin "2") (pintype "passive"))
    )
    (net (code "85") (name "DISP_LEDA") (class "Default")
      (node (ref "C109") (pin "1") (pinfunction "1_1") (pintype "passive"))
      (node (ref "D13") (pin "K") (pinfunction "K_K") (pintype "passive"))
      (node (ref "P3") (pin "25") (pintype "passive"))
      (node (ref "R134") (pin "2") (pintype "passive"))
    )
    (net (code "86") (name "DISP_LEDK1") (class "Default")
      (node (ref "P3") (pin "26") (pintype "passive"))
      (node (ref "U15") (pin "11") (pinfunction "LED1_11") (pintype "power_in"))
    )
    (net (code "87") (name "DISP_LEDK2") (class "Default")
      (node (ref "P3") (pin "27") (pintype "passive"))
      (node (ref "U15") (pin "10") (pinfunction "LED2_10") (pintype "power_in"))
    )
    (net (code "88") (name "GND") (class "Default")
      (node (ref "C103") (pin "2") (pinfunction "2_2") (pintype "passive"))
      (node (ref "C104") (pin "2") (pinfunction "2_2") (pintype "passive"))
      (node (ref "C106") (pin "2") (pinfunction "2_2") (pintype "passive"))
      (node (ref "C108") (pin "2") (pinfunction "2_2") (pintype "passive"))
      (node (ref "C109") (pin "2") (pinfunction "2_2") (pintype "passive"))
      (node (ref "C111") (pin "2") (pinfunction "2_2") (pintype "passive"))
      (node (ref "C112") (pin "2") (pinfunction "2_2") (pintype "passive"))
      (node (ref "C128") (pin "1") (pinfunction "1_1") (pintype "passive"))
      (node (ref "C129") (pin "2") (pinfunction "2_2") (pintype "passive"))
      (node (ref "C130") (pin "1") (pinfunction "1_1") (pintype "passive"))
      (node (ref "C131") (pin "1") (pinfunction "1_1") (pintype "passive"))
      (node (ref "C132") (pin "1") (pinfunction "1_1") (pintype "passive"))
      (node (ref "C52") (pin "2") (pinfunction "2_2") (pintype "passive"))
      (node (ref "C53") (pin "1") (pinfunction "1_1") (pintype "passive"))
      (node (ref "C59") (pin "1") (pinfunction "1_1") (pintype "passive"))
      (node (ref "C67") (pin "2") (pinfunction "2_2") (pintype "passive"))
      (node (ref "C69") (pin "2") (pinfunction "2_2") (pintype "passive"))
      (node (ref "ESD12") (pin "1") (pinfunction "1_1") (pintype "passive"))
      (node (ref "ESD13") (pin "1") (pinfunction "1_1") (pintype "passive"))
      (node (ref "ESD7") (pin "1") (pinfunction "1_1") (pintype "passive"))
      (node (ref "ESD8") (pin "1") (pinfunction "1_1") (pintype "passive"))
      (node (ref "J5") (pin "11") (pinfunction "CKGND_11") (pintype "bidirectional"))
      (node (ref "J5") (pin "17") (pinfunction "DDCGND_17") (pintype "bidirectional"))
      (node (ref "J5") (pin "2") (pinfunction "D2GND_2") (pintype "bidirectional"))
      (node (ref "J5") (pin "20") (pinfunction "GND1_20") (pintype "power_in"))
      (node (ref "J5") (pin "21") (pinfunction "GND2_21") (pintype "power_in"))
      (node (ref "J5") (pin "22") (pinfunction "GND3_22") (pintype "power_in"))
      (node (ref "J5") (pin "23") (pinfunction "GND4_23") (pintype "power_in"))
      (node (ref "J5") (pin "5") (pinfunction "D1GND_5") (pintype "bidirectional"))
      (node (ref "J5") (pin "8") (pinfunction "D0GND_8") (pintype "bidirectional"))
      (node (ref "P1") (pin "1") (pintype "passive"))
      (node (ref "P1") (pin "10") (pintype "passive"))
      (node (ref "P1") (pin "13") (pintype "passive"))
      (node (ref "P1") (pin "16") (pintype "passive"))
      (node (ref "P1") (pin "19") (pintype "passive"))
      (node (ref "P1") (pin "25") (pintype "passive"))
      (node (ref "P1") (pin "26") (pintype "passive"))
      (node (ref "P1") (pin "4") (pintype "passive"))
      (node (ref "P1") (pin "7") (pintype "passive"))
      (node (ref "P3") (pin "11") (pintype "passive"))
      (node (ref "P3") (pin "14") (pintype "passive"))
      (node (ref "P3") (pin "17") (pintype "passive"))
      (node (ref "P3") (pin "20") (pintype "passive"))
      (node (ref "P3") (pin "31") (pintype "passive"))
      (node (ref "P3") (pin "32") (pintype "passive"))
      (node (ref "P3") (pin "34") (pintype "passive"))
      (node (ref "P3") (pin "5") (pintype "passive"))
      (node (ref "P3") (pin "8") (pintype "passive"))
      (node (ref "P3") (pin "MT1") (pintype "passive"))
      (node (ref "P3") (pin "MT2") (pintype "passive"))
      (node (ref "Q8") (pin "1") (pinfunction "S1_1") (pintype "passive"))
      (node (ref "Q8") (pin "4") (pinfunction "S2_4") (pintype "passive"))
      (node (ref "R142") (pin "1") (pintype "passive"))
      (node (ref "R165") (pin "1") (pintype "passive"))
      (node (ref "R166") (pin "1") (pintype "passive"))
      (node (ref "R175") (pin "2") (pintype "passive"))
      (node (ref "R196") (pin "1") (pintype "passive"))
      (node (ref "R197") (pin "1") (pintype "passive"))
      (node (ref "R35") (pin "2") (pintype "passive"))
      (node (ref "R47") (pin "1") (pintype "passive"))
      (node (ref "U1") (pin "12") (pinfunction "GND_12") (pintype "power_in"))
      (node (ref "U1") (pin "20") (pinfunction "GND_20") (pintype "power_in"))
      (node (ref "U1") (pin "21") (pinfunction "GND_21") (pintype "power_in"))
      (node (ref "U1") (pin "7") (pinfunction "GND_7") (pintype "power_in"))
      (node (ref "U10") (pin "B1") (pinfunction "GND_CH1_B1") (pintype "power_in"))
      (node (ref "U10") (pin "B2") (pinfunction "GND_CH2_B2") (pintype "power_in"))
      (node (ref "U10") (pin "B3") (pinfunction "GND_CH3_B3") (pintype "power_in"))
      (node (ref "U11") (pin "B1") (pinfunction "GND_CH1_B1") (pintype "power_in"))
      (node (ref "U11") (pin "B2") (pinfunction "GND_CH2_B2") (pintype "power_in"))
      (node (ref "U15") (pin "13") (pinfunction "PGND_13") (pintype "power_in"))
      (node (ref "U15") (pin "14") (pinfunction "GND_14") (pintype "power_in"))
      (node (ref "U15") (pin "21") (pinfunction "GND_21") (pintype "power_in"))
      (node (ref "U15") (pin "5") (pinfunction "AGND_5") (pintype "power_in"))
      (node (ref "U20") (pin "11") (pinfunction "GND_11") (pintype "power_in"))
      (node (ref "U20") (pin "21") (pinfunction "GND_21") (pintype "power_in"))
      (node (ref "Y1") (pin "3") (pinfunction "GND_3") (pintype "power_in"))
    )
    (net (code "89") (name "Net-(C111-Pad1)") (class "Default")
      (node (ref "C111") (pin "1") (pinfunction "1_1") (pintype "passive"))
      (node (ref "F1") (pin "2") (pintype "passive"))
      (node (ref "P1") (pin "24") (pintype "passive"))
    )
    (net (code "90") (name "Net-(C130-Pad2)") (class "Default")
      (node (ref "C130") (pin "2") (pinfunction "2_2") (pintype "passive"))
      (node (ref "R151") (pin "1") (pintype "passive"))
    )
    (net (code "91") (name "Net-(D9-PadC)") (class "Default")
      (node (ref "D9") (pin "C") (pinfunction "C_C") (pintype "passive"))
      (node (ref "R40") (pin "2") (pintype "passive"))
      (node (ref "TP45") (pin "1") (pinfunction "1_1") (pintype "passive"))
    )
    (net (code "92") (name "Net-(D13-PadA)") (class "Default")
      (node (ref "D13") (pin "A") (pinfunction "A_A") (pintype "passive"))
      (node (ref "L4") (pin "2") (pinfunction "2_2") (pintype "passive"))
      (node (ref "U15") (pin "15") (pinfunction "LX_15") (pintype "power_in"))
      (node (ref "U15") (pin "16") (pinfunction "LX_16") (pintype "power_in"))
    )
    (net (code "93") (name "Net-(F3-Pad2)") (class "Default")
      (node (ref "F3") (pin "2") (pintype "passive"))
      (node (ref "R195") (pin "1") (pintype "passive"))
    )
    (net (code "94") (name "Net-(J5-CK+)") (class "Default")
      (node (ref "J5") (pin "10") (pinfunction "CK+_10") (pintype "bidirectional"))
      (node (ref "R188") (pin "2") (pintype "passive"))
    )
    (net (code "95") (name "Net-(J5-CK-)") (class "Default")
      (node (ref "J5") (pin "12") (pinfunction "CK-_12") (pintype "bidirectional"))
      (node (ref "R189") (pin "2") (pintype "passive"))
    )
    (net (code "96") (name "Net-(J5-D0+)") (class "Default")
      (node (ref "J5") (pin "7") (pinfunction "D0+_7") (pintype "bidirectional"))
      (node (ref "R186") (pin "2") (pintype "passive"))
    )
    (net (code "97") (name "Net-(J5-D0-)") (class "Default")
      (node (ref "J5") (pin "9") (pinfunction "D0-_9") (pintype "bidirectional"))
      (node (ref "R187") (pin "2") (pintype "passive"))
    )
    (net (code "98") (name "Net-(J5-D1+)") (class "Default")
      (node (ref "J5") (pin "4") (pinfunction "D1+_4") (pintype "bidirectional"))
      (node (ref "R184") (pin "2") (pintype "passive"))
    )
    (net (code "99") (name "Net-(J5-D1-)") (class "Default")
      (node (ref "J5") (pin "6") (pinfunction "D1-_6") (pintype "bidirectional"))
      (node (ref "R185") (pin "2") (pintype "passive"))
    )
    (net (code "100") (name "Net-(J5-D2+)") (class "Default")
      (node (ref "J5") (pin "1") (pinfunction "D2+_1") (pintype "bidirectional"))
      (node (ref "R182") (pin "2") (pintype "passive"))
    )
    (net (code "101") (name "Net-(J5-D2-)") (class "Default")
      (node (ref "J5") (pin "3") (pinfunction "D2-_3") (pintype "bidirectional"))
      (node (ref "R183") (pin "2") (pintype "passive"))
    )
    (net (code "102") (name "Net-(P3-Pad4)") (class "Default")
      (node (ref "P3") (pin "4") (pintype "passive"))
      (node (ref "TP2") (pin "1") (pinfunction "1_1") (pintype "passive"))
    )
    (net (code "103") (name "Net-(P3-Pad33)") (class "Default")
      (node (ref "P3") (pin "33") (pintype "passive"))
      (node (ref "TP21") (pin "1") (pinfunction "1_1") (pintype "passive"))
    )
    (net (code "104") (name "Net-(P3-Pad37)") (class "Default")
      (node (ref "P3") (pin "37") (pintype "passive"))
      (node (ref "R190") (pin "2") (pintype "passive"))
    )
    (net (code "105") (name "Net-(Q8A-D1)") (class "Default")
      (node (ref "Q8") (pin "6") (pinfunction "D1_6") (pintype "passive"))
      (node (ref "R41") (pin "1") (pintype "passive"))
      (node (ref "R42") (pin "1") (pintype "passive"))
      (node (ref "R43") (pin "1") (pintype "passive"))
      (node (ref "R44") (pin "1") (pintype "passive"))
    )
    (net (code "106") (name "Net-(Q8B-D2)") (class "Default")
      (node (ref "Q8") (pin "3") (pinfunction "D2_3") (pintype "passive"))
      (node (ref "R48") (pin "1") (pintype "passive"))
      (node (ref "R49") (pin "1") (pintype "passive"))
      (node (ref "R50") (pin "1") (pintype "passive"))
      (node (ref "R51") (pin "1") (pintype "passive"))
    )
    (net (code "107") (name "Net-(U1-C1N)") (class "Default")
      (node (ref "C29") (pin "2") (pinfunction "2_2") (pintype "passive"))
      (node (ref "U1") (pin "10") (pinfunction "C1N_10") (pintype "power_in"))
    )
    (net (code "108") (name "Net-(U1-C1P)") (class "Default")
      (node (ref "C29") (pin "1") (pinfunction "1_1") (pintype "passive"))
      (node (ref "U1") (pin "11") (pinfunction "C1P_11") (pintype "power_in"))
    )
    (net (code "109") (name "Net-(U1-C2N)") (class "Default")
      (node (ref "C96") (pin "2") (pinfunction "2_2") (pintype "passive"))
      (node (ref "U1") (pin "13") (pinfunction "C2N_13") (pintype "power_in"))
    )
    (net (code "110") (name "Net-(U1-C2P)") (class "Default")
      (node (ref "C96") (pin "1") (pinfunction "1_1") (pintype "passive"))
      (node (ref "U1") (pin "14") (pinfunction "C2P_14") (pintype "power_in"))
    )
    (net (code "111") (name "Net-(U1-C3N)") (class "Default")
      (node (ref "C105") (pin "1") (pinfunction "1_1") (pintype "passive"))
      (node (ref "U1") (pin "16") (pinfunction "C3N_16") (pintype "power_in"))
    )
    (net (code "112") (name "Net-(U1-C3P)") (class "Default")
      (node (ref "C105") (pin "2") (pinfunction "2_2") (pintype "passive"))
      (node (ref "U1") (pin "17") (pinfunction "C3P_17") (pintype "power_in"))
    )
    (net (code "113") (name "Net-(U1-C4N)") (class "Default")
      (node (ref "C107") (pin "2") (pinfunction "2_2") (pintype "passive"))
      (node (ref "U1") (pin "2") (pinfunction "C4N_2") (pintype "power_in"))
    )
    (net (code "114") (name "Net-(U1-C4P)") (class "Default")
      (node (ref "C107") (pin "1") (pinfunction "1_1") (pintype "passive"))
      (node (ref "U1") (pin "1") (pinfunction "C4P_1") (pintype "power_in"))
    )
    (net (code "115") (name "Net-(U1-EN)") (class "Default")
      (node (ref "R36") (pin "2") (pintype "passive"))
      (node (ref "U1") (pin "3") (pinfunction "EN_3") (pintype "input"))
    )
    (net (code "116") (name "Net-(U1-FBN)") (class "Default")
      (node (ref "R131") (pin "2") (pintype "passive"))
      (node (ref "R37") (pin "2") (pintype "passive"))
      (node (ref "U1") (pin "5") (pinfunction "FBN_5") (pintype "power_in"))
    )
    (net (code "117") (name "Net-(U1-FBP)") (class "Default")
      (node (ref "R34") (pin "2") (pintype "passive"))
      (node (ref "R35") (pin "1") (pintype "passive"))
      (node (ref "U1") (pin "19") (pinfunction "FBP_19") (pintype "power_in"))
    )
    (net (code "118") (name "Net-(U1-VREF)") (class "Default")
      (node (ref "C69") (pin "1") (pinfunction "1_1") (pintype "passive"))
      (node (ref "R131") (pin "1") (pintype "passive"))
      (node (ref "U1") (pin "6") (pinfunction "VREF_6") (pintype "power_in"))
    )
    (net (code "119") (name "Net-(U15-COMP)") (class "Default")
      (node (ref "R151") (pin "2") (pintype "passive"))
      (node (ref "U15") (pin "20") (pinfunction "COMP_20") (pintype "passive"))
    )
    (net (code "120") (name "Net-(U15-EN)") (class "Default")
      (node (ref "R143") (pin "2") (pintype "passive"))
      (node (ref "U15") (pin "1") (pinfunction "EN_1") (pintype "input"))
    )
    (net (code "121") (name "Net-(U15-MIX)") (class "Default")
      (node (ref "R175") (pin "1") (pintype "passive"))
      (node (ref "U15") (pin "4") (pinfunction "MIX_4") (pintype "passive"))
    )
    (net (code "122") (name "Net-(U15-OVP)") (class "Default")
      (node (ref "C112") (pin "1") (pinfunction "1_1") (pintype "passive"))
      (node (ref "R134") (pin "1") (pintype "passive"))
      (node (ref "R142") (pin "2") (pintype "passive"))
      (node (ref "U15") (pin "12") (pinfunction "OVP_12") (pintype "power_in"))
    )
    (net (code "123") (name "Net-(U15-PWM)") (class "Default")
      (node (ref "R150") (pin "2") (pintype "passive"))
      (node (ref "U15") (pin "17") (pinfunction "PWM_17") (pintype "passive"))
    )
    (net (code "124") (name "Net-(U15-VDC)") (class "Default")
      (node (ref "C129") (pin "1") (pinfunction "1_1") (pintype "passive"))
      (node (ref "U15") (pin "18") (pinfunction "VDC_18") (pintype "power_in"))
    )
    (net (code "125") (name "Net-(U15-VIN)") (class "Default")
      (node (ref "C128") (pin "2") (pinfunction "2_2") (pintype "passive"))
      (node (ref "R135") (pin "2") (pintype "passive"))
      (node (ref "U15") (pin "19") (pinfunction "VIN_19") (pintype "power_in"))
    )
    (net (code "126") (name "Net-(U20-B3)") (class "Default")
      (node (ref "R169") (pin "1") (pintype "passive"))
      (node (ref "U20") (pin "17") (pinfunction "B3_17") (pintype "passive"))
    )
    (net (code "127") (name "Net-(U20-B4)") (class "Default")
      (node (ref "R170") (pin "1") (pintype "passive"))
      (node (ref "U20") (pin "16") (pinfunction "B4_16") (pintype "passive"))
    )
    (net (code "128") (name "Net-(U20-B5)") (class "Default")
      (node (ref "R171") (pin "1") (pintype "passive"))
      (node (ref "U20") (pin "15") (pinfunction "B5_15") (pintype "passive"))
    )
    (net (code "129") (name "Net-(U20-B6)") (class "Default")
      (node (ref "R172") (pin "1") (pintype "passive"))
      (node (ref "U20") (pin "14") (pinfunction "B6_14") (pintype "passive"))
    )
    (net (code "130") (name "Net-(U20-OE)") (class "Default")
      (node (ref "R211") (pin "1") (pintype "passive"))
      (node (ref "U20") (pin "10") (pinfunction "OE_10") (pintype "passive"))
    )
    (net (code "131") (name "Net-(Y1-NC)") (class "Default")
      (node (ref "R45") (pin "1") (pintype "passive"))
      (node (ref "Y1") (pin "2") (pinfunction "NC_2") (pintype "input"))
    )
    (net (code "132") (name "Net-(Y1-OE)") (class "Default")
      (node (ref "R46") (pin "1") (pintype "passive"))
      (node (ref "Y1") (pin "1") (pinfunction "OE_1") (pintype "passive"))
    )
    (net (code "133") (name "V1V8") (class "Default")
      (node (ref "C131") (pin "2") (pinfunction "2_2") (pintype "passive"))
      (node (ref "P3") (pin "23") (pintype "passive"))
      (node (ref "Q8") (pin "2") (pinfunction "G1_2") (pintype "passive"))
      (node (ref "Q8") (pin "5") (pinfunction "G2_5") (pintype "passive"))
      (node (ref "R167") (pin "2") (pintype "passive"))
      (node (ref "R168") (pin "2") (pintype "passive"))
      (node (ref "R211") (pin "2") (pintype "passive"))
      (node (ref "U20") (pin "2") (pinfunction "VCCa_2") (pintype "passive"))
    )
    (net (code "134") (name "V3V3") (class "Default")
      (node (ref "C104") (pin "1") (pinfunction "1_1") (pintype "passive"))
      (node (ref "C132") (pin "2") (pinfunction "2_2") (pintype "passive"))
      (node (ref "C59") (pin "2") (pinfunction "2_2") (pintype "passive"))
      (node (ref "D9") (pin "A") (pinfunction "A_A") (pintype "passive"))
      (node (ref "F1") (pin "1") (pintype "passive"))
      (node (ref "R45") (pin "2") (pintype "passive"))
      (node (ref "R46") (pin "2") (pintype "passive"))
      (node (ref "U1") (pin "8") (pinfunction "VIN_8") (pintype "power_in"))
      (node (ref "U20") (pin "19") (pinfunction "VCCb_19") (pintype "power_in"))
      (node (ref "Y1") (pin "6") (pinfunction "VCC_6") (pintype "power_in"))
    )
    (net (code "135") (name "VON_N5p5") (class "Default")
      (node (ref "C106") (pin "1") (pinfunction "1_1") (pintype "passive"))
      (node (ref "R152") (pin "1") (pintype "passive"))
      (node (ref "R37") (pin "1") (pintype "passive"))
      (node (ref "U1") (pin "4") (pinfunction "VON_4") (pintype "passive"))
    )
    (net (code "136") (name "VOP_5p5") (class "Default")
      (node (ref "C103") (pin "1") (pinfunction "1_1") (pintype "passive"))
      (node (ref "C67") (pin "1") (pinfunction "1_1") (pintype "passive"))
      (node (ref "R153") (pin "1") (pintype "passive"))
      (node (ref "R34") (pin "1") (pintype "passive"))
      (node (ref "U1") (pin "18") (pinfunction "VOP_18") (pintype "power_in"))
    )
    (net (code "137") (name "unconnected-(P1-Pad18)") (class "Default")
      (node (ref "P1") (pin "18") (pintype "passive+no_connect"))
    )
    (net (code "138") (name "unconnected-(P1-Pad22)") (class "Default")
      (node (ref "P1") (pin "22") (pintype "passive+no_connect"))
    )
    (net (code "139") (name "unconnected-(P3-Pad1)") (class "Default")
      (node (ref "P3") (pin "1") (pintype "passive+no_connect"))
    )
    (net (code "140") (name "unconnected-(P3-Pad22)") (class "Default")
      (node (ref "P3") (pin "22") (pintype "passive+no_connect"))
    )
    (net (code "141") (name "unconnected-(P3-Pad24)") (class "Default")
      (node (ref "P3") (pin "24") (pintype "passive+no_connect"))
    )
    (net (code "142") (name "unconnected-(U1-NC-Pad9)") (class "Default")
      (node (ref "U1") (pin "9") (pinfunction "NC_9") (pintype "passive+no_connect"))
    )
    (net (code "143") (name "unconnected-(U1-NC-Pad15)") (class "Default")
      (node (ref "U1") (pin "15") (pinfunction "NC_15") (pintype "passive+no_connect"))
    )
    (net (code "144") (name "unconnected-(U15-LED3-Pad9)") (class "Default")
      (node (ref "U15") (pin "9") (pinfunction "LED3_9") (pintype "power_in+no_connect"))
    )
    (net (code "145") (name "unconnected-(U15-LED4-Pad8)") (class "Default")
      (node (ref "U15") (pin "8") (pinfunction "LED4_8") (pintype "power_in+no_connect"))
    )
    (net (code "146") (name "unconnected-(U15-LED5-Pad7)") (class "Default")
      (node (ref "U15") (pin "7") (pinfunction "LED5_7") (pintype "power_in+no_connect"))
    )
    (net (code "147") (name "unconnected-(U15-LED6-Pad6)") (class "Default")
      (node (ref "U15") (pin "6") (pinfunction "LED6_6") (pintype "power_in+no_connect"))
    )
    (net (code "148") (name "unconnected-(U20-A7-Pad8)") (class "Default")
      (node (ref "U20") (pin "8") (pinfunction "A7_8") (pintype "passive+no_connect"))
    )
    (net (code "149") (name "unconnected-(U20-A8-Pad9)") (class "Default")
      (node (ref "U20") (pin "9") (pinfunction "A8_9") (pintype "passive+no_connect"))
    )
    (net (code "150") (name "unconnected-(U20-B7-Pad13)") (class "Default")
      (node (ref "U20") (pin "13") (pinfunction "B7_13") (pintype "passive+no_connect"))
    )
    (net (code "151") (name "unconnected-(U20-B8-Pad12)") (class "Default")
      (node (ref "U20") (pin "12") (pinfunction "B8_12") (pintype "passive+no_connect"))
    )
  )
)
